# SolarRS485-V1_1.net
KiCad netlist of a schematic drawn in EAGLE
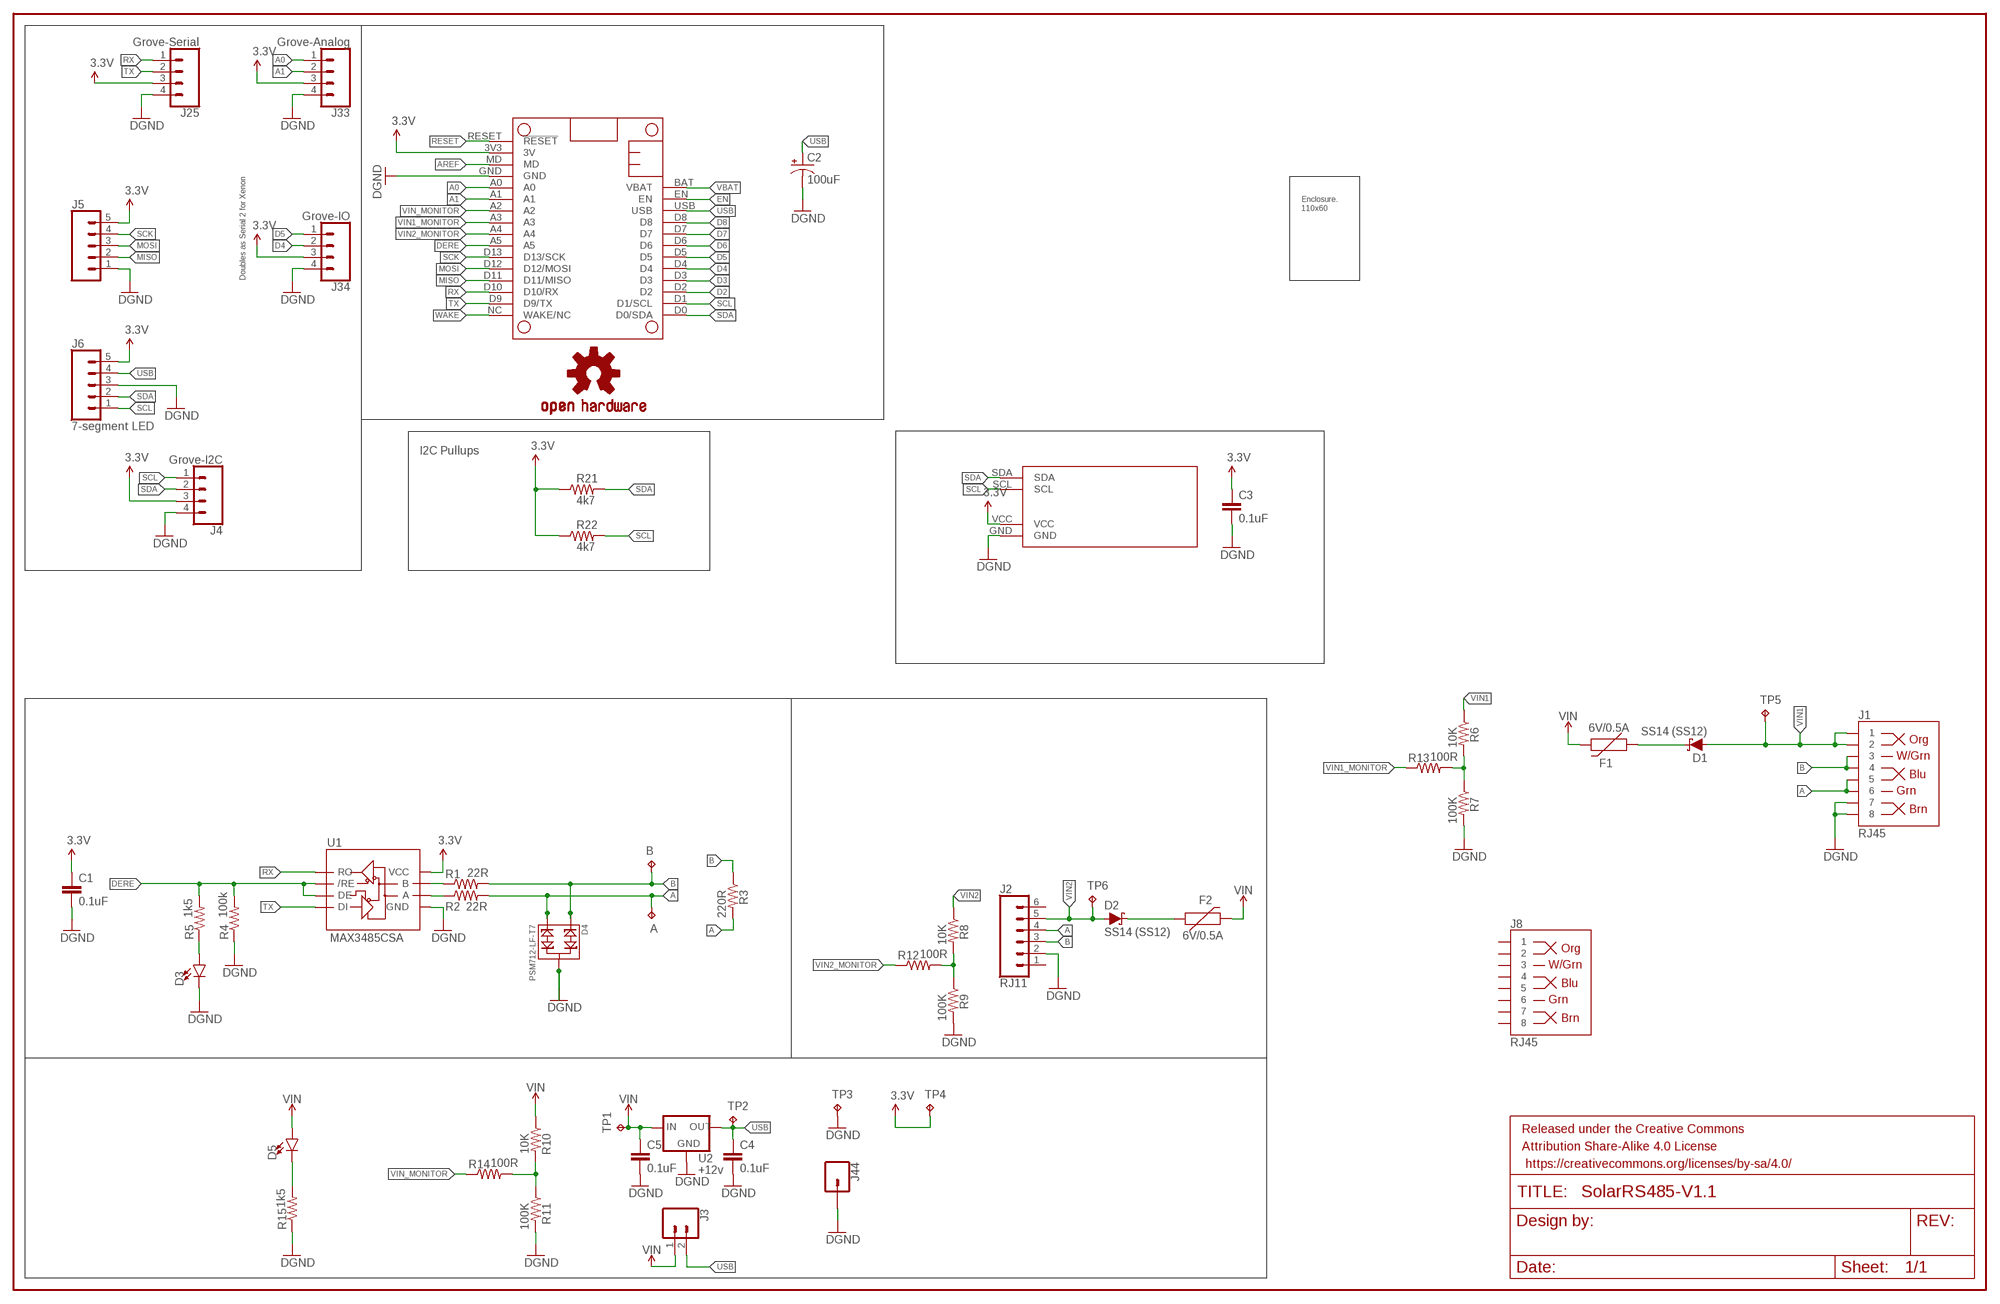
[diagram p0: schematic, sheet 1]

(export (version "E")
  (design (tool "Eeschema 10.0.6"))
  (components
    (comp (ref "A")
      (value "TPTP15R")
      (footprint "eagle-import:TP15R")
      (libsource (lib "eagle-import") (part "TPTP15R"))
    )
    (comp (ref "B")
      (value "TPTP15R")
      (footprint "eagle-import:TP15R")
      (libsource (lib "eagle-import") (part "TPTP15R"))
    )
    (comp (ref "C1")
      (value "0.1uF")
      (footprint "eagle-import:0805")
      (libsource (lib "eagle-import") (part "0.1UF-0805-25V"))
    )
    (comp (ref "C2")
      (value "100uF")
      (footprint "eagle-import:CPOL-RADIAL-2.5MM-6.5MM")
      (libsource (lib "eagle-import") (part "100UF-POLAR-RADIAL-2.5MM-25V-20%"))
    )
    (comp (ref "C3")
      (value "0.1uF")
      (footprint "eagle-import:0805")
      (libsource (lib "eagle-import") (part "0.1UF-0805-25V"))
    )
    (comp (ref "C4")
      (value "0.1uF")
      (footprint "eagle-import:0805")
      (libsource (lib "eagle-import") (part "0.1UF-0805-25V"))
    )
    (comp (ref "C5")
      (value "0.1uF")
      (footprint "eagle-import:0805")
      (libsource (lib "eagle-import") (part "0.1UF-0805-25V"))
    )
    (comp (ref "D1")
      (value "SS14 (SS12)")
      (footprint "eagle-import:SMA-DIODE")
      (libsource (lib "eagle-import") (part "DIODE-SCHOTTKY-SS14"))
    )
    (comp (ref "D2")
      (value "SS14 (SS12)")
      (footprint "eagle-import:SMA-DIODE")
      (libsource (lib "eagle-import") (part "DIODE-SCHOTTKY-SS14"))
    )
    (comp (ref "D3")
      (value "LEDLED-1206-BOTTOM-2.0MM-BLUE")
      (footprint "eagle-import:LED-1206-BOTTOM-2.0MM")
      (libsource (lib "eagle-import") (part "LEDLED-1206-BOTTOM-2.0MM-BLUE"))
    )
    (comp (ref "D4")
      (value "PSM712-LF-T7")
      (footprint "eagle-import:SOT-23")
      (fields (field (name "MPN") "CESD5V0AP"))
      (libsource (lib "eagle-import") (part "SMD-DIODE-TVS-5V-225MW(SOT-23)"))
    )
    (comp (ref "D5")
      (value "LED1206")
      (footprint "eagle-import:LED-1206")
      (libsource (lib "eagle-import") (part "LED1206"))
    )
    (comp (ref "F1")
      (value "6V/0.5A")
      (footprint "eagle-import:1206")
      (libsource (lib "eagle-import") (part "PPTC_HALF-AMP"))
    )
    (comp (ref "F2")
      (value "6V/0.5A")
      (footprint "eagle-import:1206")
      (libsource (lib "eagle-import") (part "PPTC_HALF-AMP"))
    )
    (comp (ref "FRAME2")
      (value "FRAME-LEDGER")
      (footprint "eagle-import:CREATIVE_COMMONS")
      (libsource (lib "eagle-import") (part "FRAME-LEDGER"))
    )
    (comp (ref "J1")
      (value "RJ45")
      (footprint "eagle-import:RJ45-8")
      (libsource (lib "eagle-import") (part "RJ45-8"))
    )
    (comp (ref "J2")
      (value "RJ11")
      (footprint "eagle-import:RJ11-6")
      (libsource (lib "eagle-import") (part "RJ11-6"))
    )
    (comp (ref "J3")
      (value "CONN_02")
      (footprint "eagle-import:1X02")
      (libsource (lib "eagle-import") (part "CONN_02"))
    )
    (comp (ref "J4")
      (value "Grove-I2C")
      (footprint "eagle-import:JST-4-PH-GROVE")
      (libsource (lib "eagle-import") (part "CONN_04GROVE-JST-PH-4-2MM"))
    )
    (comp (ref "J5")
      (value "CONN_05")
      (footprint "eagle-import:1X05")
      (libsource (lib "eagle-import") (part "CONN_05"))
    )
    (comp (ref "J6")
      (value "7-segment LED")
      (footprint "eagle-import:1X05")
      (libsource (lib "eagle-import") (part "CONN_05"))
    )
    (comp (ref "J8")
      (value "RJ45")
      (footprint "eagle-import:RJ45-8")
      (libsource (lib "eagle-import") (part "RJ45-8"))
    )
    (comp (ref "J25")
      (value "Grove-Serial")
      (footprint "eagle-import:JST-4-PH-GROVE")
      (libsource (lib "eagle-import") (part "CONN_04GROVE-JST-PH-4-2MM"))
    )
    (comp (ref "J33")
      (value "Grove-Analog")
      (footprint "eagle-import:JST-4-PH-GROVE")
      (libsource (lib "eagle-import") (part "CONN_04GROVE-JST-PH-4-2MM"))
    )
    (comp (ref "J34")
      (value "Grove-IO")
      (footprint "eagle-import:JST-4-PH-GROVE")
      (libsource (lib "eagle-import") (part "CONN_04GROVE-JST-PH-4-2MM"))
    )
    (comp (ref "J44")
      (value "CONN_01PTH_NO_SILK_YES_STOP")
      (footprint "eagle-import:1X01_NO_SILK")
      (libsource (lib "eagle-import") (part "CONN_01PTH_NO_SILK_YES_STOP"))
    )
    (comp (ref "LOGO1")
      (value "OSHW-LOGOM")
      (footprint "eagle-import:OSHW-LOGO-M")
      (libsource (lib "eagle-import") (part "OSHW-LOGOM"))
    )
    (comp (ref "MS1")
      (value "XENONA")
      (footprint "eagle-import:XENON_BREAKOUT_A")
      (libsource (lib "eagle-import") (part "XENONA"))
    )
    (comp (ref "R1")
      (value "22R")
      (footprint "eagle-import:0805")
      (libsource (lib "eagle-import") (part "RESISTOR0805"))
    )
    (comp (ref "R2")
      (value "22R")
      (footprint "eagle-import:0805")
      (libsource (lib "eagle-import") (part "RESISTOR0805"))
    )
    (comp (ref "R3")
      (value "220R")
      (footprint "eagle-import:0805")
      (libsource (lib "eagle-import") (part "RESISTOR0805"))
    )
    (comp (ref "R4")
      (value "100k")
      (footprint "eagle-import:0805")
      (libsource (lib "eagle-import") (part "RESISTOR0805"))
    )
    (comp (ref "R5")
      (value "1k5")
      (footprint "eagle-import:0805")
      (libsource (lib "eagle-import") (part "RESISTOR0805"))
    )
    (comp (ref "R6")
      (value "10K")
      (footprint "eagle-import:0805")
      (libsource (lib "eagle-import") (part "RESISTOR0805"))
    )
    (comp (ref "R7")
      (value "100K")
      (footprint "eagle-import:0805")
      (libsource (lib "eagle-import") (part "RESISTOR0805"))
    )
    (comp (ref "R8")
      (value "10K")
      (footprint "eagle-import:0805")
      (libsource (lib "eagle-import") (part "RESISTOR0805"))
    )
    (comp (ref "R9")
      (value "100K")
      (footprint "eagle-import:0805")
      (libsource (lib "eagle-import") (part "RESISTOR0805"))
    )
    (comp (ref "R10")
      (value "10K")
      (footprint "eagle-import:0805")
      (libsource (lib "eagle-import") (part "RESISTOR0805"))
    )
    (comp (ref "R11")
      (value "100K")
      (footprint "eagle-import:0805")
      (libsource (lib "eagle-import") (part "RESISTOR0805"))
    )
    (comp (ref "R12")
      (value "100R")
      (footprint "eagle-import:0805")
      (libsource (lib "eagle-import") (part "RESISTOR0805"))
    )
    (comp (ref "R13")
      (value "100R")
      (footprint "eagle-import:0805")
      (libsource (lib "eagle-import") (part "RESISTOR0805"))
    )
    (comp (ref "R14")
      (value "100R")
      (footprint "eagle-import:0805")
      (libsource (lib "eagle-import") (part "RESISTOR0805"))
    )
    (comp (ref "R15")
      (value "1k5")
      (footprint "eagle-import:0805")
      (libsource (lib "eagle-import") (part "RESISTOR0805"))
    )
    (comp (ref "R21")
      (value "4k7")
      (footprint "eagle-import:0805")
      (libsource (lib "eagle-import") (part "RESISTOR0805"))
    )
    (comp (ref "R22")
      (value "4k7")
      (footprint "eagle-import:0805")
      (libsource (lib "eagle-import") (part "RESISTOR0805"))
    )
    (comp (ref "TP1")
      (value "TPTP15R")
      (footprint "eagle-import:TP15R")
      (libsource (lib "eagle-import") (part "TPTP15R"))
    )
    (comp (ref "TP2")
      (value "TPTP15R")
      (footprint "eagle-import:TP15R")
      (libsource (lib "eagle-import") (part "TPTP15R"))
    )
    (comp (ref "TP3")
      (value "TPTP15R")
      (footprint "eagle-import:TP15R")
      (libsource (lib "eagle-import") (part "TPTP15R"))
    )
    (comp (ref "TP4")
      (value "TPTP15R")
      (footprint "eagle-import:TP15R")
      (libsource (lib "eagle-import") (part "TPTP15R"))
    )
    (comp (ref "TP5")
      (value "TPTP15R")
      (footprint "eagle-import:TP15R")
      (libsource (lib "eagle-import") (part "TPTP15R"))
    )
    (comp (ref "TP6")
      (value "TPTP15R")
      (footprint "eagle-import:TP15R")
      (libsource (lib "eagle-import") (part "TPTP15R"))
    )
    (comp (ref "U$1")
      (value "CAMDENBOSS-ENCLOSURE-110X60BOTH-EXTENDED-WIDE")
      (footprint "eagle-import:CAMDENBOSS_ENCLOSURE_110X60_WIDE_EXTENDED")
      (libsource (lib "eagle-import") (part "CAMDENBOSS-ENCLOSURE-110X60BOTH-EXTENDED-WIDE"))
    )
    (comp (ref "U$2")
      (value "DISPLAY0.96_INCH_DISPLAY")
      (footprint "eagle-import:I2C_DISPLAY_0.96_INCH")
      (libsource (lib "eagle-import") (part "DISPLAY0.96_INCH_DISPLAY"))
    )
    (comp (ref "U1")
      (value "MAX3485CSA")
      (footprint "eagle-import:SO08")
      (libsource (lib "eagle-import") (part "RS485SOIC"))
    )
    (comp (ref "U2")
      (value "+12v")
      (footprint "eagle-import:TO-252")
      (libsource (lib "eagle-import") (part "V_REG_78XX7812"))
    )
  )
  (nets
    (net (code "1") (name "3.3V") (class "Default")
      (node (ref "C1") (pin "1") (pinfunction "1_1") (pintype "passive"))
      (node (ref "C3") (pin "1") (pinfunction "1_1") (pintype "passive"))
      (node (ref "J25") (pin "3") (pinfunction "3_3") (pintype "passive"))
      (node (ref "J33") (pin "3") (pinfunction "3_3") (pintype "passive"))
      (node (ref "J34") (pin "3") (pinfunction "3_3") (pintype "passive"))
      (node (ref "J4") (pin "3") (pinfunction "3_3") (pintype "passive"))
      (node (ref "J5") (pin "5") (pinfunction "5_5") (pintype "passive"))
      (node (ref "J6") (pin "5") (pinfunction "5_5") (pintype "passive"))
      (node (ref "MS1") (pin "3V3") (pinfunction "3V_3V3") (pintype "power_in"))
      (node (ref "R21") (pin "1") (pinfunction "1_1") (pintype "passive"))
      (node (ref "R22") (pin "1") (pinfunction "1_1") (pintype "passive"))
      (node (ref "TP4") (pin "TP") (pinfunction "TP_TP") (pintype "input"))
      (node (ref "U$2") (pin "VCC") (pinfunction "VCC_VCC") (pintype "power_in"))
      (node (ref "U1") (pin "8") (pinfunction "VCC_8") (pintype "bidirectional"))
    )
    (net (code "2") (name "A") (class "Default")
      (node (ref "A") (pin "TP") (pinfunction "TP_TP") (pintype "input"))
      (node (ref "D4") (pin "2") (pinfunction "2_2") (pintype "power_in"))
      (node (ref "J1") (pin "5") (pinfunction "5_5") (pintype "bidirectional"))
      (node (ref "J1") (pin "6") (pinfunction "6_6") (pintype "bidirectional"))
      (node (ref "J2") (pin "4") (pinfunction "4_4") (pintype "passive"))
      (node (ref "R2") (pin "2") (pinfunction "2_2") (pintype "passive"))
      (node (ref "R3") (pin "2") (pinfunction "2_2") (pintype "passive"))
    )
    (net (code "3") (name "A0") (class "Default")
      (node (ref "J33") (pin "1") (pinfunction "1_1") (pintype "passive"))
      (node (ref "MS1") (pin "A0") (pinfunction "A0_A0") (pintype "bidirectional"))
    )
    (net (code "4") (name "A1") (class "Default")
      (node (ref "J33") (pin "2") (pinfunction "2_2") (pintype "passive"))
      (node (ref "MS1") (pin "A1") (pinfunction "A1_A1") (pintype "bidirectional"))
    )
    (net (code "5") (name "AREF") (class "Default")
      (node (ref "MS1") (pin "MD") (pinfunction "MD_MD") (pintype "passive"))
    )
    (net (code "6") (name "B") (class "Default")
      (node (ref "B") (pin "TP") (pinfunction "TP_TP") (pintype "input"))
      (node (ref "D4") (pin "1") (pinfunction "1_1") (pintype "power_in"))
      (node (ref "J1") (pin "3") (pinfunction "3_3") (pintype "bidirectional"))
      (node (ref "J1") (pin "4") (pinfunction "4_4") (pintype "bidirectional"))
      (node (ref "J2") (pin "3") (pinfunction "3_3") (pintype "passive"))
      (node (ref "R1") (pin "2") (pinfunction "2_2") (pintype "passive"))
      (node (ref "R3") (pin "1") (pinfunction "1_1") (pintype "passive"))
    )
    (net (code "7") (name "D2") (class "Default")
      (node (ref "MS1") (pin "D2") (pinfunction "D2_D2") (pintype "bidirectional"))
    )
    (net (code "8") (name "D3") (class "Default")
      (node (ref "MS1") (pin "D3") (pinfunction "D3_D3") (pintype "bidirectional"))
    )
    (net (code "9") (name "D4") (class "Default")
      (node (ref "J34") (pin "2") (pinfunction "2_2") (pintype "passive"))
      (node (ref "MS1") (pin "D4") (pinfunction "D4_D4") (pintype "bidirectional"))
    )
    (net (code "10") (name "D5") (class "Default")
      (node (ref "J34") (pin "1") (pinfunction "1_1") (pintype "passive"))
      (node (ref "MS1") (pin "D5") (pinfunction "D5_D5") (pintype "bidirectional"))
    )
    (net (code "11") (name "D6") (class "Default")
      (node (ref "MS1") (pin "D6") (pinfunction "D6_D6") (pintype "bidirectional"))
    )
    (net (code "12") (name "D7") (class "Default")
      (node (ref "MS1") (pin "D7") (pinfunction "D7_D7") (pintype "bidirectional"))
    )
    (net (code "13") (name "D8") (class "Default")
      (node (ref "MS1") (pin "D8") (pinfunction "D8_D8") (pintype "bidirectional"))
    )
    (net (code "14") (name "DERE") (class "Default")
      (node (ref "MS1") (pin "A5") (pinfunction "A5_A5") (pintype "bidirectional"))
      (node (ref "R4") (pin "2") (pinfunction "2_2") (pintype "passive"))
      (node (ref "R5") (pin "2") (pinfunction "2_2") (pintype "passive"))
      (node (ref "U1") (pin "2") (pinfunction "/RE_2") (pintype "bidirectional"))
      (node (ref "U1") (pin "3") (pinfunction "DE_3") (pintype "bidirectional"))
    )
    (net (code "15") (name "DGND") (class "Default")
      (node (ref "C1") (pin "2") (pinfunction "2_2") (pintype "passive"))
      (node (ref "C2") (pin "2") (pinfunction "-_2") (pintype "passive"))
      (node (ref "C3") (pin "2") (pinfunction "2_2") (pintype "passive"))
      (node (ref "C4") (pin "2") (pinfunction "2_2") (pintype "passive"))
      (node (ref "C5") (pin "2") (pinfunction "2_2") (pintype "passive"))
      (node (ref "D3") (pin "C") (pinfunction "C_C") (pintype "passive"))
      (node (ref "D4") (pin "3") (pinfunction "3_3") (pintype "bidirectional"))
      (node (ref "J1") (pin "7") (pinfunction "7_7") (pintype "bidirectional"))
      (node (ref "J1") (pin "8") (pinfunction "8_8") (pintype "bidirectional"))
      (node (ref "J2") (pin "2") (pinfunction "2_2") (pintype "passive"))
      (node (ref "J25") (pin "4") (pinfunction "4_4") (pintype "passive"))
      (node (ref "J33") (pin "4") (pinfunction "4_4") (pintype "passive"))
      (node (ref "J34") (pin "4") (pinfunction "4_4") (pintype "passive"))
      (node (ref "J4") (pin "4") (pinfunction "4_4") (pintype "passive"))
      (node (ref "J44") (pin "1") (pinfunction "1_1") (pintype "passive"))
      (node (ref "J5") (pin "1") (pinfunction "1_1") (pintype "passive"))
      (node (ref "J6") (pin "3") (pinfunction "3_3") (pintype "passive"))
      (node (ref "MS1") (pin "GND") (pinfunction "GND_GND") (pintype "power_in"))
      (node (ref "R11") (pin "2") (pinfunction "2_2") (pintype "passive"))
      (node (ref "R15") (pin "1") (pinfunction "1_1") (pintype "passive"))
      (node (ref "R4") (pin "1") (pinfunction "1_1") (pintype "passive"))
      (node (ref "R7") (pin "2") (pinfunction "2_2") (pintype "passive"))
      (node (ref "R9") (pin "2") (pinfunction "2_2") (pintype "passive"))
      (node (ref "TP3") (pin "TP") (pinfunction "TP_TP") (pintype "input"))
      (node (ref "U$2") (pin "GND") (pinfunction "GND_GND") (pintype "power_in"))
      (node (ref "U1") (pin "5") (pinfunction "GND_5") (pintype "bidirectional"))
      (node (ref "U2") (pin "3") (pinfunction "GND_3") (pintype "input"))
    )
    (net (code "16") (name "EN") (class "Default")
      (node (ref "MS1") (pin "EN") (pinfunction "EN_EN") (pintype "passive"))
    )
    (net (code "17") (name "MISO") (class "Default")
      (node (ref "J5") (pin "2") (pinfunction "2_2") (pintype "passive"))
      (node (ref "MS1") (pin "D11") (pinfunction "D11/MISO_D11") (pintype "bidirectional"))
    )
    (net (code "18") (name "MOSI") (class "Default")
      (node (ref "J5") (pin "3") (pinfunction "3_3") (pintype "passive"))
      (node (ref "MS1") (pin "D12") (pinfunction "D12/MOSI_D12") (pintype "bidirectional"))
    )
    (net (code "19") (name "Net-(D1-PadC)") (class "Default")
      (node (ref "D1") (pin "C") (pinfunction "C_C") (pintype "passive"))
      (node (ref "F1") (pin "1") (pinfunction "1_1") (pintype "bidirectional"))
    )
    (net (code "20") (name "Net-(D2-PadC)") (class "Default")
      (node (ref "D2") (pin "C") (pinfunction "C_C") (pintype "passive"))
      (node (ref "F2") (pin "1") (pinfunction "1_1") (pintype "bidirectional"))
    )
    (net (code "21") (name "Net-(D3-PadA)") (class "Default")
      (node (ref "D3") (pin "A") (pinfunction "A_A") (pintype "passive"))
      (node (ref "R5") (pin "1") (pinfunction "1_1") (pintype "passive"))
    )
    (net (code "22") (name "Net-(D5-PadC)") (class "Default")
      (node (ref "D5") (pin "C") (pinfunction "C_C") (pintype "passive"))
      (node (ref "R15") (pin "2") (pinfunction "2_2") (pintype "passive"))
    )
    (net (code "23") (name "Net-(R10-Pad2)") (class "Default")
      (node (ref "R10") (pin "2") (pinfunction "2_2") (pintype "passive"))
      (node (ref "R11") (pin "1") (pinfunction "1_1") (pintype "passive"))
      (node (ref "R14") (pin "2") (pinfunction "2_2") (pintype "passive"))
    )
    (net (code "24") (name "Net-(R12-Pad2)") (class "Default")
      (node (ref "R12") (pin "2") (pinfunction "2_2") (pintype "passive"))
      (node (ref "R8") (pin "2") (pinfunction "2_2") (pintype "passive"))
      (node (ref "R9") (pin "1") (pinfunction "1_1") (pintype "passive"))
    )
    (net (code "25") (name "Net-(R13-Pad2)") (class "Default")
      (node (ref "R13") (pin "2") (pinfunction "2_2") (pintype "passive"))
      (node (ref "R6") (pin "2") (pinfunction "2_2") (pintype "passive"))
      (node (ref "R7") (pin "1") (pinfunction "1_1") (pintype "passive"))
    )
    (net (code "26") (name "Net-(U1-A)") (class "Default")
      (node (ref "R2") (pin "1") (pinfunction "1_1") (pintype "passive"))
      (node (ref "U1") (pin "6") (pinfunction "A_6") (pintype "bidirectional"))
    )
    (net (code "27") (name "Net-(U1-B)") (class "Default")
      (node (ref "R1") (pin "1") (pinfunction "1_1") (pintype "passive"))
      (node (ref "U1") (pin "7") (pinfunction "B_7") (pintype "bidirectional"))
    )
    (net (code "28") (name "RESET") (class "Default")
      (node (ref "MS1") (pin "RESET") (pinfunction "~{RESET}_RESET") (pintype "input"))
    )
    (net (code "29") (name "RX") (class "Default")
      (node (ref "J25") (pin "1") (pinfunction "1_1") (pintype "passive"))
      (node (ref "MS1") (pin "D10") (pinfunction "D10/RX_D10") (pintype "bidirectional"))
      (node (ref "U1") (pin "1") (pinfunction "RO_1") (pintype "bidirectional"))
    )
    (net (code "30") (name "SCK") (class "Default")
      (node (ref "J5") (pin "4") (pinfunction "4_4") (pintype "passive"))
      (node (ref "MS1") (pin "D13") (pinfunction "D13/SCK_D13") (pintype "bidirectional"))
    )
    (net (code "31") (name "SCL") (class "Default")
      (node (ref "J4") (pin "1") (pinfunction "1_1") (pintype "passive"))
      (node (ref "J6") (pin "1") (pinfunction "1_1") (pintype "passive"))
      (node (ref "MS1") (pin "D1") (pinfunction "D1/SCL_D1") (pintype "bidirectional"))
      (node (ref "R22") (pin "2") (pinfunction "2_2") (pintype "passive"))
      (node (ref "U$2") (pin "SCL") (pinfunction "SCL_SCL") (pintype "bidirectional"))
    )
    (net (code "32") (name "SDA") (class "Default")
      (node (ref "J4") (pin "2") (pinfunction "2_2") (pintype "passive"))
      (node (ref "J6") (pin "2") (pinfunction "2_2") (pintype "passive"))
      (node (ref "MS1") (pin "D0") (pinfunction "D0/SDA_D0") (pintype "bidirectional"))
      (node (ref "R21") (pin "2") (pinfunction "2_2") (pintype "passive"))
      (node (ref "U$2") (pin "SDA") (pinfunction "SDA_SDA") (pintype "bidirectional"))
    )
    (net (code "33") (name "TX") (class "Default")
      (node (ref "J25") (pin "2") (pinfunction "2_2") (pintype "passive"))
      (node (ref "MS1") (pin "D9") (pinfunction "D9/TX_D9") (pintype "bidirectional"))
      (node (ref "U1") (pin "4") (pinfunction "DI_4") (pintype "bidirectional"))
    )
    (net (code "34") (name "USB") (class "Default")
      (node (ref "C2") (pin "1") (pinfunction "+_1") (pintype "passive"))
      (node (ref "C4") (pin "1") (pinfunction "1_1") (pintype "passive"))
      (node (ref "J3") (pin "2") (pinfunction "2_2") (pintype "passive"))
      (node (ref "J6") (pin "4") (pinfunction "4_4") (pintype "passive"))
      (node (ref "MS1") (pin "USB") (pinfunction "USB_USB") (pintype "power_in"))
      (node (ref "TP2") (pin "TP") (pinfunction "TP_TP") (pintype "input"))
      (node (ref "U2") (pin "2") (pinfunction "OUT_2") (pintype "passive"))
    )
    (net (code "35") (name "VBAT") (class "Default")
      (node (ref "MS1") (pin "BAT") (pinfunction "VBAT_BAT") (pintype "power_in"))
    )
    (net (code "36") (name "VIN") (class "Default")
      (node (ref "C5") (pin "1") (pinfunction "1_1") (pintype "passive"))
      (node (ref "D5") (pin "A") (pinfunction "A_A") (pintype "passive"))
      (node (ref "F1") (pin "2") (pinfunction "2_2") (pintype "bidirectional"))
      (node (ref "F2") (pin "2") (pinfunction "2_2") (pintype "bidirectional"))
      (node (ref "J3") (pin "1") (pinfunction "1_1") (pintype "passive"))
      (node (ref "R10") (pin "1") (pinfunction "1_1") (pintype "passive"))
      (node (ref "TP1") (pin "TP") (pinfunction "TP_TP") (pintype "input"))
      (node (ref "U2") (pin "1") (pinfunction "IN_1") (pintype "input"))
    )
    (net (code "37") (name "VIN1") (class "Default")
      (node (ref "D1") (pin "A") (pinfunction "A_A") (pintype "passive"))
      (node (ref "J1") (pin "1") (pinfunction "1_1") (pintype "bidirectional"))
      (node (ref "J1") (pin "2") (pinfunction "2_2") (pintype "bidirectional"))
      (node (ref "R6") (pin "1") (pinfunction "1_1") (pintype "passive"))
      (node (ref "TP5") (pin "TP") (pinfunction "TP_TP") (pintype "input"))
    )
    (net (code "38") (name "VIN1_MONITOR") (class "Default")
      (node (ref "MS1") (pin "A3") (pinfunction "A3_A3") (pintype "bidirectional"))
      (node (ref "R13") (pin "1") (pinfunction "1_1") (pintype "passive"))
    )
    (net (code "39") (name "VIN2") (class "Default")
      (node (ref "D2") (pin "A") (pinfunction "A_A") (pintype "passive"))
      (node (ref "J2") (pin "5") (pinfunction "5_5") (pintype "passive"))
      (node (ref "R8") (pin "1") (pinfunction "1_1") (pintype "passive"))
      (node (ref "TP6") (pin "TP") (pinfunction "TP_TP") (pintype "input"))
    )
    (net (code "40") (name "VIN2_MONITOR") (class "Default")
      (node (ref "MS1") (pin "A4") (pinfunction "A4_A4") (pintype "bidirectional"))
      (node (ref "R12") (pin "1") (pinfunction "1_1") (pintype "passive"))
    )
    (net (code "41") (name "VIN_MONITOR") (class "Default")
      (node (ref "MS1") (pin "A2") (pinfunction "A2_A2") (pintype "bidirectional"))
      (node (ref "R14") (pin "1") (pinfunction "1_1") (pintype "passive"))
    )
    (net (code "42") (name "WAKE") (class "Default")
      (node (ref "MS1") (pin "NC") (pinfunction "WAKE/NC_NC") (pintype "passive"))
    )
    (net (code "43") (name "unconnected-(J2-Pad1)") (class "Default")
      (node (ref "J2") (pin "1") (pinfunction "1_1") (pintype "passive"))
    )
    (net (code "44") (name "unconnected-(J2-Pad6)") (class "Default")
      (node (ref "J2") (pin "6") (pinfunction "6_6") (pintype "passive"))
    )
    (net (code "45") (name "unconnected-(J8-Pad1)") (class "Default")
      (node (ref "J8") (pin "1") (pinfunction "1_1") (pintype "bidirectional"))
    )
    (net (code "46") (name "unconnected-(J8-Pad2)") (class "Default")
      (node (ref "J8") (pin "2") (pinfunction "2_2") (pintype "bidirectional"))
    )
    (net (code "47") (name "unconnected-(J8-Pad3)") (class "Default")
      (node (ref "J8") (pin "3") (pinfunction "3_3") (pintype "bidirectional"))
    )
    (net (code "48") (name "unconnected-(J8-Pad4)") (class "Default")
      (node (ref "J8") (pin "4") (pinfunction "4_4") (pintype "bidirectional"))
    )
    (net (code "49") (name "unconnected-(J8-Pad5)") (class "Default")
      (node (ref "J8") (pin "5") (pinfunction "5_5") (pintype "bidirectional"))
    )
    (net (code "50") (name "unconnected-(J8-Pad6)") (class "Default")
      (node (ref "J8") (pin "6") (pinfunction "6_6") (pintype "bidirectional"))
    )
    (net (code "51") (name "unconnected-(J8-Pad7)") (class "Default")
      (node (ref "J8") (pin "7") (pinfunction "7_7") (pintype "bidirectional"))
    )
    (net (code "52") (name "unconnected-(J8-Pad8)") (class "Default")
      (node (ref "J8") (pin "8") (pinfunction "8_8") (pintype "bidirectional"))
    )
  )
)
